# LEDMatrixMC.net
KiCad netlist of a schematic drawn in EAGLE
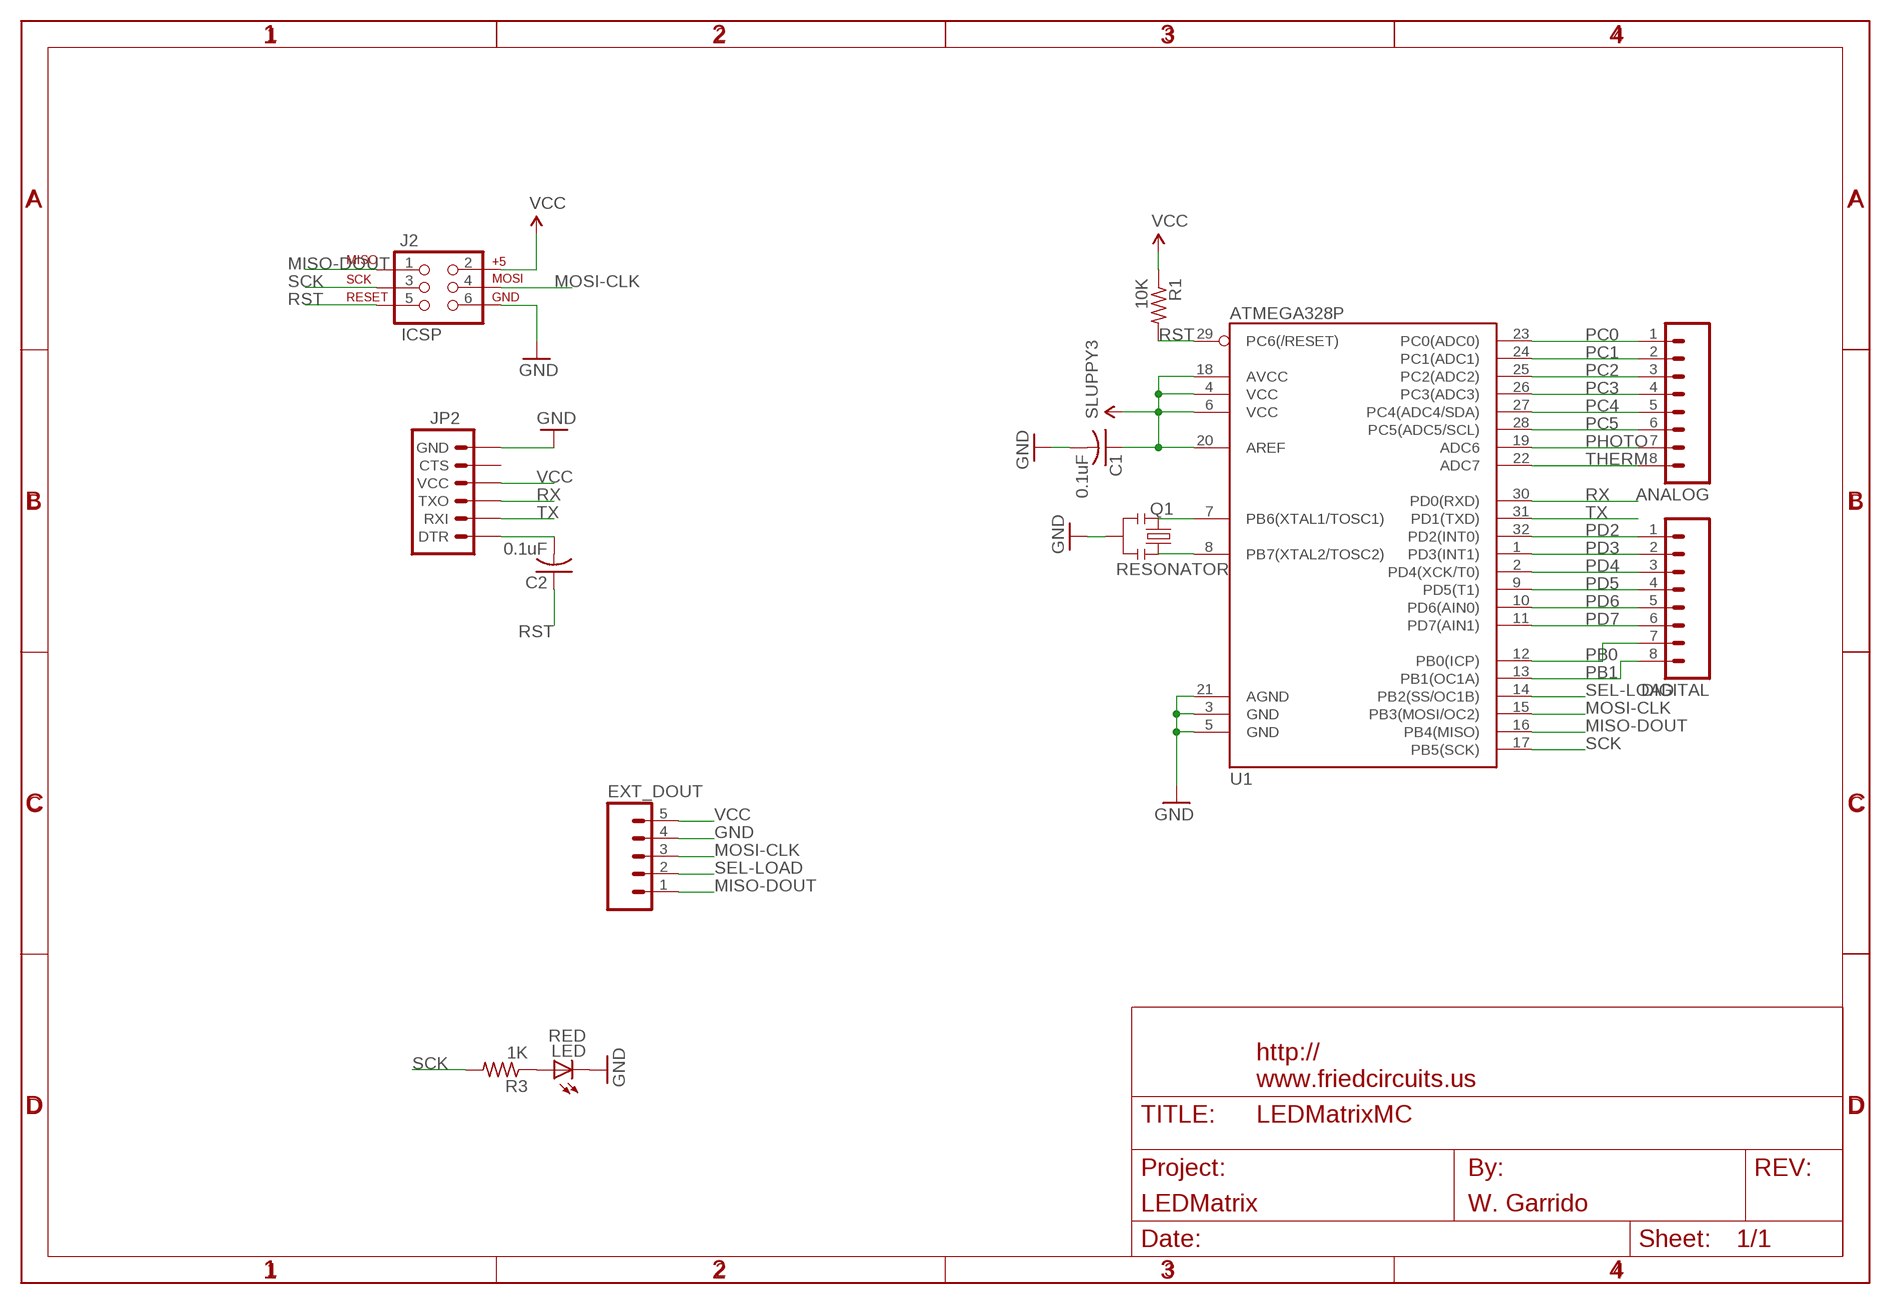
[diagram p0: schematic, sheet 1]

(export (version "E")
  (design (tool "Eeschema 10.0.6"))
  (components
    (comp (ref "ANALOG")
      (value "M08LOCK")
      (footprint "eagle-import:1X08_LOCK")
      (libsource (lib "eagle-import") (part "M08LOCK"))
    )
    (comp (ref "C1")
      (value "0.1uF")
      (footprint "eagle-import:C0805K")
      (libsource (lib "eagle-import") (part "C-USC0805K"))
    )
    (comp (ref "C2")
      (value "0.1uF")
      (footprint "eagle-import:C0805K")
      (libsource (lib "eagle-import") (part "C-USC0805K"))
    )
    (comp (ref "DIGITAL")
      (value "M08LOCK")
      (footprint "eagle-import:1X08_LOCK")
      (libsource (lib "eagle-import") (part "M08LOCK"))
    )
    (comp (ref "EXT_DOUT")
      (value "M05LOCK_LONGPADS")
      (footprint "eagle-import:1X05_LOCK_LONGPADS")
      (libsource (lib "eagle-import") (part "M05LOCK_LONGPADS"))
    )
    (comp (ref "J2")
      (value "ICSP")
      (footprint "eagle-import:2X3_LOCK")
      (libsource (lib "eagle-import") (part "AVR_SPI_PRG_62X3_LOCK"))
    )
    (comp (ref "JP2")
      (value "ARDUINO_SERIAL_PROGRAMLOCK")
      (footprint "eagle-import:1X06_LOCK")
      (libsource (lib "eagle-import") (part "ARDUINO_SERIAL_PROGRAMLOCK"))
    )
    (comp (ref "LED")
      (value "RED")
      (footprint "eagle-import:CHIPLED_0805")
      (libsource (lib "eagle-import") (part "LEDCHIPLED_0805"))
    )
    (comp (ref "Q1")
      (value "RESONATOR")
      (footprint "eagle-import:RESONATOR-SMD")
      (libsource (lib "eagle-import") (part "RESONATORSMD"))
    )
    (comp (ref "R1")
      (value "10K")
      (footprint "eagle-import:R0805")
      (libsource (lib "eagle-import") (part "R-US_R0805"))
    )
    (comp (ref "R3")
      (value "1K")
      (footprint "eagle-import:R0805")
      (libsource (lib "eagle-import") (part "R-US_R0805"))
    )
    (comp (ref "U$1")
      (value "FRAME_DINA4_L")
      (footprint "eagle-import:FC_CREDIT")
      (fields (field (name "PROJECT") "LEDMatrix") (field (name "AUTHOR") "W. Garrido"))
      (libsource (lib "eagle-import") (part "FRAME_DINA4_L"))
    )
    (comp (ref "U1")
      (value "ATMEGA328P")
      (footprint "eagle-import:TQFP32-08")
      (libsource (lib "eagle-import") (part "ATMEGA328_SMT"))
    )
  )
  (nets
    (net (code "1") (name "/MISO-DOUT") (class "Default")
      (node (ref "EXT_DOUT") (pin "1") (pinfunction "1_1") (pintype "passive"))
      (node (ref "J2") (pin "1") (pinfunction "1_1") (pintype "passive"))
      (node (ref "U1") (pin "16") (pinfunction "PB4(MISO)_16") (pintype "bidirectional"))
    )
    (net (code "2") (name "/MOSI-CLK") (class "Default")
      (node (ref "EXT_DOUT") (pin "3") (pinfunction "3_3") (pintype "passive"))
      (node (ref "J2") (pin "4") (pinfunction "4_4") (pintype "passive"))
      (node (ref "U1") (pin "15") (pinfunction "PB3(MOSI/OC2)_15") (pintype "bidirectional"))
    )
    (net (code "3") (name "/PB0") (class "Default")
      (node (ref "DIGITAL") (pin "7") (pinfunction "7_7") (pintype "passive"))
      (node (ref "U1") (pin "12") (pinfunction "PB0(ICP)_12") (pintype "bidirectional"))
    )
    (net (code "4") (name "/PB1") (class "Default")
      (node (ref "DIGITAL") (pin "8") (pinfunction "8_8") (pintype "passive"))
      (node (ref "U1") (pin "13") (pinfunction "PB1(OC1A)_13") (pintype "bidirectional"))
    )
    (net (code "5") (name "/PC0") (class "Default")
      (node (ref "ANALOG") (pin "1") (pinfunction "1_1") (pintype "passive"))
      (node (ref "U1") (pin "23") (pinfunction "PC0(ADC0)_23") (pintype "bidirectional"))
    )
    (net (code "6") (name "/PC1") (class "Default")
      (node (ref "ANALOG") (pin "2") (pinfunction "2_2") (pintype "passive"))
      (node (ref "U1") (pin "24") (pinfunction "PC1(ADC1)_24") (pintype "bidirectional"))
    )
    (net (code "7") (name "/PC2") (class "Default")
      (node (ref "ANALOG") (pin "3") (pinfunction "3_3") (pintype "passive"))
      (node (ref "U1") (pin "25") (pinfunction "PC2(ADC2)_25") (pintype "bidirectional"))
    )
    (net (code "8") (name "/PC3") (class "Default")
      (node (ref "ANALOG") (pin "4") (pinfunction "4_4") (pintype "passive"))
      (node (ref "U1") (pin "26") (pinfunction "PC3(ADC3)_26") (pintype "bidirectional"))
    )
    (net (code "9") (name "/PC4") (class "Default")
      (node (ref "ANALOG") (pin "5") (pinfunction "5_5") (pintype "passive"))
      (node (ref "U1") (pin "27") (pinfunction "PC4(ADC4/SDA)_27") (pintype "bidirectional"))
    )
    (net (code "10") (name "/PC5") (class "Default")
      (node (ref "ANALOG") (pin "6") (pinfunction "6_6") (pintype "passive"))
      (node (ref "U1") (pin "28") (pinfunction "PC5(ADC5/SCL)_28") (pintype "bidirectional"))
    )
    (net (code "11") (name "/PD2") (class "Default")
      (node (ref "DIGITAL") (pin "1") (pinfunction "1_1") (pintype "passive"))
      (node (ref "U1") (pin "32") (pinfunction "PD2(INT0)_32") (pintype "bidirectional"))
    )
    (net (code "12") (name "/PD3") (class "Default")
      (node (ref "DIGITAL") (pin "2") (pinfunction "2_2") (pintype "passive"))
      (node (ref "U1") (pin "1") (pinfunction "PD3(INT1)_1") (pintype "bidirectional"))
    )
    (net (code "13") (name "/PD4") (class "Default")
      (node (ref "DIGITAL") (pin "3") (pinfunction "3_3") (pintype "passive"))
      (node (ref "U1") (pin "2") (pinfunction "PD4(XCK/T0)_2") (pintype "bidirectional"))
    )
    (net (code "14") (name "/PD5") (class "Default")
      (node (ref "DIGITAL") (pin "4") (pinfunction "4_4") (pintype "passive"))
      (node (ref "U1") (pin "9") (pinfunction "PD5(T1)_9") (pintype "bidirectional"))
    )
    (net (code "15") (name "/PD6") (class "Default")
      (node (ref "DIGITAL") (pin "5") (pinfunction "5_5") (pintype "passive"))
      (node (ref "U1") (pin "10") (pinfunction "PD6(AIN0)_10") (pintype "bidirectional"))
    )
    (net (code "16") (name "/PD7") (class "Default")
      (node (ref "DIGITAL") (pin "6") (pinfunction "6_6") (pintype "passive"))
      (node (ref "U1") (pin "11") (pinfunction "PD7(AIN1)_11") (pintype "bidirectional"))
    )
    (net (code "17") (name "/PHOTO") (class "Default")
      (node (ref "ANALOG") (pin "7") (pinfunction "7_7") (pintype "passive"))
      (node (ref "U1") (pin "19") (pinfunction "ADC6_19") (pintype "bidirectional"))
    )
    (net (code "18") (name "/RST") (class "Default")
      (node (ref "C2") (pin "1") (pinfunction "1_1") (pintype "passive"))
      (node (ref "J2") (pin "5") (pinfunction "5_5") (pintype "passive"))
      (node (ref "R1") (pin "2") (pinfunction "2_2") (pintype "passive"))
      (node (ref "U1") (pin "29") (pinfunction "PC6(/RESET)_29") (pintype "bidirectional"))
    )
    (net (code "19") (name "/RX") (class "Default")
      (node (ref "JP2") (pin "3") (pinfunction "TXO_3") (pintype "passive"))
      (node (ref "U1") (pin "30") (pinfunction "PD0(RXD)_30") (pintype "bidirectional"))
    )
    (net (code "20") (name "/SCK") (class "Default")
      (node (ref "J2") (pin "3") (pinfunction "3_3") (pintype "passive"))
      (node (ref "R3") (pin "2") (pinfunction "2_2") (pintype "passive"))
      (node (ref "U1") (pin "17") (pinfunction "PB5(SCK)_17") (pintype "bidirectional"))
    )
    (net (code "21") (name "/SEL-LOAD") (class "Default")
      (node (ref "EXT_DOUT") (pin "2") (pinfunction "2_2") (pintype "passive"))
      (node (ref "U1") (pin "14") (pinfunction "PB2(SS/OC1B)_14") (pintype "bidirectional"))
    )
    (net (code "22") (name "/THERM") (class "Default")
      (node (ref "ANALOG") (pin "8") (pinfunction "8_8") (pintype "passive"))
      (node (ref "U1") (pin "22") (pinfunction "ADC7_22") (pintype "bidirectional"))
    )
    (net (code "23") (name "/TX") (class "Default")
      (node (ref "JP2") (pin "2") (pinfunction "RXI_2") (pintype "passive"))
      (node (ref "U1") (pin "31") (pinfunction "PD1(TXD)_31") (pintype "bidirectional"))
    )
    (net (code "24") (name "GND") (class "Default")
      (node (ref "C1") (pin "2") (pinfunction "2_2") (pintype "passive"))
      (node (ref "EXT_DOUT") (pin "4") (pinfunction "4_4") (pintype "passive"))
      (node (ref "J2") (pin "6") (pinfunction "6_6") (pintype "passive"))
      (node (ref "JP2") (pin "6") (pinfunction "GND_6") (pintype "passive"))
      (node (ref "LED") (pin "C") (pinfunction "C_C") (pintype "passive"))
      (node (ref "Q1") (pin "2") (pinfunction "2_2") (pintype "passive"))
      (node (ref "U1") (pin "21") (pinfunction "AGND_21") (pintype "bidirectional"))
      (node (ref "U1") (pin "3") (pinfunction "GND_3") (pintype "bidirectional"))
      (node (ref "U1") (pin "5") (pinfunction "GND_5") (pintype "bidirectional"))
    )
    (net (code "25") (name "Net-(JP2-DTR)") (class "Default")
      (node (ref "C2") (pin "2") (pinfunction "2_2") (pintype "passive"))
      (node (ref "JP2") (pin "1") (pinfunction "DTR_1") (pintype "passive"))
    )
    (net (code "26") (name "Net-(LED-PadA)") (class "Default")
      (node (ref "LED") (pin "A") (pinfunction "A_A") (pintype "passive"))
      (node (ref "R3") (pin "1") (pinfunction "1_1") (pintype "passive"))
    )
    (net (code "27") (name "Net-(U1-PB6(XTAL1{slash}TOSC1))") (class "Default")
      (node (ref "Q1") (pin "3") (pinfunction "3_3") (pintype "passive"))
      (node (ref "U1") (pin "7") (pinfunction "PB6(XTAL1/TOSC1)_7") (pintype "bidirectional"))
    )
    (net (code "28") (name "Net-(U1-PB7(XTAL2{slash}TOSC2))") (class "Default")
      (node (ref "Q1") (pin "1") (pinfunction "1_1") (pintype "passive"))
      (node (ref "U1") (pin "8") (pinfunction "PB7(XTAL2/TOSC2)_8") (pintype "bidirectional"))
    )
    (net (code "29") (name "SLUPPY3") (class "Default")
      (node (ref "C1") (pin "1") (pinfunction "1_1") (pintype "passive"))
      (node (ref "EXT_DOUT") (pin "5") (pinfunction "5_5") (pintype "passive"))
      (node (ref "J2") (pin "2") (pinfunction "2_2") (pintype "passive"))
      (node (ref "JP2") (pin "4") (pinfunction "VCC_4") (pintype "passive"))
      (node (ref "R1") (pin "1") (pinfunction "1_1") (pintype "passive"))
      (node (ref "U1") (pin "18") (pinfunction "AVCC_18") (pintype "bidirectional"))
      (node (ref "U1") (pin "20") (pinfunction "AREF_20") (pintype "bidirectional"))
      (node (ref "U1") (pin "4") (pinfunction "VCC_4") (pintype "bidirectional"))
      (node (ref "U1") (pin "6") (pinfunction "VCC_6") (pintype "bidirectional"))
    )
    (net (code "30") (name "unconnected-(JP2-CTS-Pad5)") (class "Default")
      (node (ref "JP2") (pin "5") (pinfunction "CTS_5") (pintype "passive"))
    )
  )
)
